# channelswitcher_unify.net
KiCad netlist of a schematic drawn in EAGLE
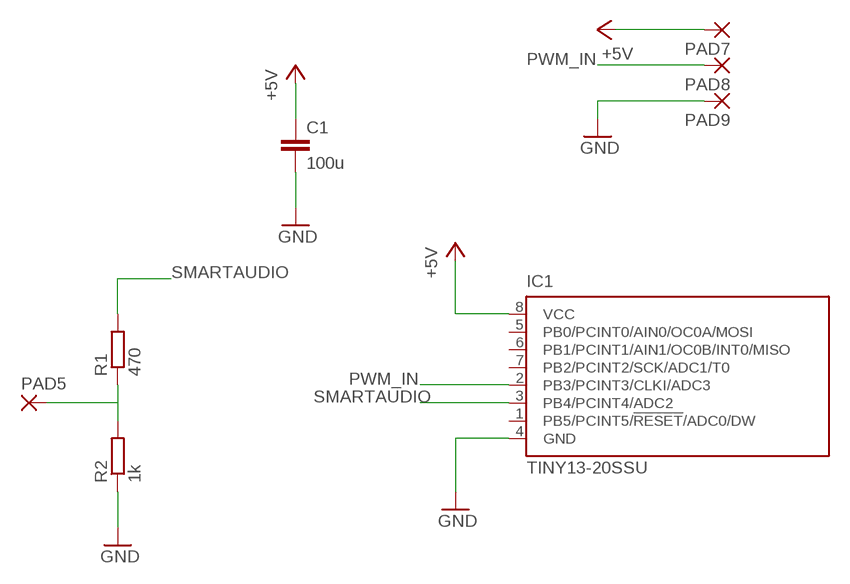
[diagram p0: schematic, sheet 1]

(export (version "E")
  (design (tool "Eeschema 10.0.6"))
  (components
    (comp (ref "C1")
      (value "100u")
      (footprint "eagle-import:C0805")
      (libsource (lib "eagle-import") (part "C-EUC0805"))
    )
    (comp (ref "IC1")
      (value "TINY13-20SSU")
      (footprint "eagle-import:8S1")
      (fields (field (name "MPN") "ATTINY13-20SSU"))
      (libsource (lib "eagle-import") (part "TINY13SSU-20"))
    )
    (comp (ref "PAD5")
      (value "SMD2")
      (footprint "eagle-import:SMD1,27-2,54")
      (libsource (lib "eagle-import") (part "SMD2"))
    )
    (comp (ref "PAD7")
      (value "SMD2")
      (footprint "eagle-import:SMD1,27-2,54")
      (libsource (lib "eagle-import") (part "SMD2"))
    )
    (comp (ref "PAD8")
      (value "SMD2")
      (footprint "eagle-import:SMD1,27-2,54")
      (libsource (lib "eagle-import") (part "SMD2"))
    )
    (comp (ref "PAD9")
      (value "SMD2")
      (footprint "eagle-import:SMD1,27-2,54")
      (libsource (lib "eagle-import") (part "SMD2"))
    )
    (comp (ref "R1")
      (value "470")
      (footprint "eagle-import:R0805")
      (libsource (lib "eagle-import") (part "R-EU_R0805"))
    )
    (comp (ref "R2")
      (value "1k")
      (footprint "eagle-import:R0805")
      (libsource (lib "eagle-import") (part "R-EU_R0805"))
    )
  )
  (nets
    (net (code "1") (name "+5V") (class "Default")
      (node (ref "C1") (pin "1") (pinfunction "1_1") (pintype "passive"))
      (node (ref "IC1") (pin "8") (pinfunction "VCC_8") (pintype "power_in"))
      (node (ref "PAD7") (pin "1") (pinfunction "P_1") (pintype "passive"))
    )
    (net (code "2") (name "/PWM_IN") (class "Default")
      (node (ref "IC1") (pin "2") (pinfunction "PB3/PCINT3/CLKI/ADC3_2") (pintype "bidirectional"))
      (node (ref "PAD8") (pin "1") (pinfunction "P_1") (pintype "passive"))
    )
    (net (code "3") (name "/SMARTAUDIO") (class "Default")
      (node (ref "IC1") (pin "3") (pinfunction "PB4/PCINT4/ADC2_3") (pintype "bidirectional"))
      (node (ref "R1") (pin "2") (pinfunction "2_2") (pintype "passive"))
    )
    (net (code "4") (name "GND") (class "Default")
      (node (ref "C1") (pin "2") (pinfunction "2_2") (pintype "passive"))
      (node (ref "IC1") (pin "4") (pinfunction "GND_4") (pintype "power_in"))
      (node (ref "PAD9") (pin "1") (pinfunction "P_1") (pintype "passive"))
      (node (ref "R2") (pin "1") (pinfunction "1_1") (pintype "passive"))
    )
    (net (code "5") (name "Net-(PAD5-P)") (class "Default")
      (node (ref "PAD5") (pin "1") (pinfunction "P_1") (pintype "passive"))
      (node (ref "R1") (pin "1") (pinfunction "1_1") (pintype "passive"))
      (node (ref "R2") (pin "2") (pinfunction "2_2") (pintype "passive"))
    )
    (net (code "6") (name "unconnected-(IC1-PB0{slash}PCINT0{slash}AIN0{slash}OC0A{slash}MOSI-Pad5)") (class "Default")
      (node (ref "IC1") (pin "5") (pinfunction "PB0/PCINT0/AIN0/OC0A/MOSI_5") (pintype "bidirectional"))
    )
    (net (code "7") (name "unconnected-(IC1-PB1{slash}PCINT1{slash}AIN1{slash}OC0B{slash}INT0{slash}MISO-Pad6)") (class "Default")
      (node (ref "IC1") (pin "6") (pinfunction "PB1/PCINT1/AIN1/OC0B/INT0/MISO_6") (pintype "bidirectional"))
    )
    (net (code "8") (name "unconnected-(IC1-PB2{slash}PCINT2{slash}SCK{slash}ADC1{slash}T0-Pad7)") (class "Default")
      (node (ref "IC1") (pin "7") (pinfunction "PB2/PCINT2/SCK/ADC1/T0_7") (pintype "bidirectional"))
    )
    (net (code "9") (name "unconnected-(IC1-PB5{slash}PCINT5{slash}~{RESET}{slash}ADC0{slash}DW-Pad1)") (class "Default")
      (node (ref "IC1") (pin "1") (pinfunction "PB5/PCINT5/~{RESET}/ADC0/DW_1") (pintype "bidirectional"))
    )
  )
)
